# 3_Communication_Buffers.net
KiCad netlist of a schematic drawn in Altium Designer
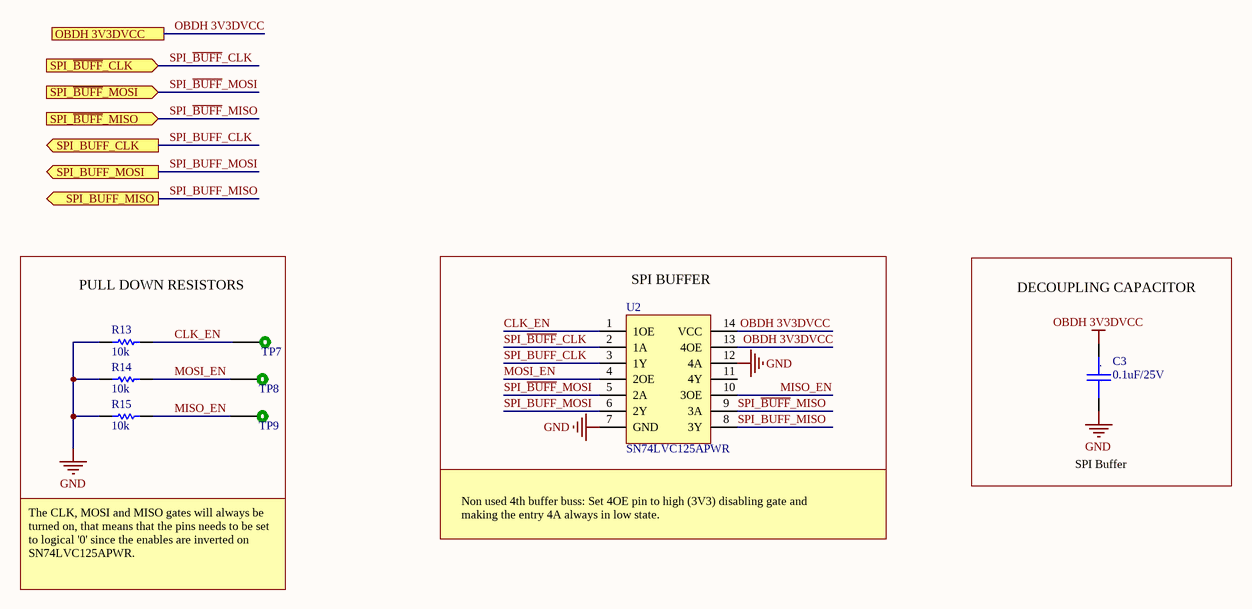
[diagram p0: 3_Communication_Buffers.SchDoc]

(export (version "E")
  (design (tool "Eeschema 10.0.6"))
  (components
    (comp (ref "C3")
      (value "0.1uF/25V")
      (footprint "C0805_MD")
      (description "CAP CER 0.1UF 25V 10% X7R 0805")
      (fields (field (name "PARTNUMBER") "CC0805KRX7R8BB104") (field (name "MANUFACTURER") "Yageo"))
      (libsource (lib "Memory_Expansion_Daughter_Board_SchLib") (part "Cap_Cer_X7R_0.1uF_25V_0805"))
    )
    (comp (ref "R13")
      (value "10k")
      (footprint "0805")
      (description "RES 10K OHM 1/8W 1%  0805")
      (fields (field (name "PARTNUMBER") "CRCW080510K0FKEA") (field (name "MANUFACTURER") "Vishay"))
      (libsource (lib "Memory_Expansion_Daughter_Board_SchLib") (part "R10k_1%_1/8W_0805"))
    )
    (comp (ref "R14")
      (value "10k")
      (footprint "0805")
      (description "RES 10K OHM 1/8W 1%  0805")
      (fields (field (name "PARTNUMBER") "CRCW080510K0FKEA") (field (name "MANUFACTURER") "Vishay"))
      (libsource (lib "Memory_Expansion_Daughter_Board_SchLib") (part "R10k_1%_1/8W_0805"))
    )
    (comp (ref "R15")
      (value "10k")
      (footprint "0805")
      (description "RES 10K OHM 1/8W 1%  0805")
      (fields (field (name "PARTNUMBER") "CRCW080510K0FKEA") (field (name "MANUFACTURER") "Vishay"))
      (libsource (lib "Memory_Expansion_Daughter_Board_SchLib") (part "R10k_1%_1/8W_0805"))
    )
    (comp (ref "TP7")
      (value "TEST_POINT_2")
      (footprint "TEST_POINT_2")
      (description "Test point")
      (libsource (lib "Memory_Expansion_Daughter_Board_SchLib") (part "TEST_POINT_2"))
    )
    (comp (ref "TP8")
      (value "TEST_POINT_2")
      (footprint "TEST_POINT_2")
      (description "Test point")
      (libsource (lib "Memory_Expansion_Daughter_Board_SchLib") (part "TEST_POINT_2"))
    )
    (comp (ref "TP9")
      (value "TEST_POINT_2")
      (footprint "TEST_POINT_2")
      (description "Test point")
      (libsource (lib "Memory_Expansion_Daughter_Board_SchLib") (part "TEST_POINT_2"))
    )
    (comp (ref "U2")
      (value "SN74LVC125APWR")
      (footprint "SN74LVC125APWR")
      (description "IC BUF NON-INVERT 3.6V 14TSSOP")
      (fields (field (name "MANUFACTURER") "Texas Instruments"))
      (libsource (lib "Memory_Expansion_Daughter_Board_SchLib") (part "SN74LVC125APWR"))
    )
  )
  (nets
    (net (code "1") (name "/CLK_EN") (class "Default")
      (node (ref "R13") (pin "1") (pinfunction "1_1") (pintype "passive"))
      (node (ref "TP7") (pin "1") (pinfunction "1_1") (pintype "passive"))
      (node (ref "U2") (pin "1") (pinfunction "1OE_1") (pintype "passive"))
    )
    (net (code "2") (name "/MISO_EN") (class "Default")
      (node (ref "R15") (pin "1") (pinfunction "1_1") (pintype "passive"))
      (node (ref "TP9") (pin "1") (pinfunction "1_1") (pintype "passive"))
      (node (ref "U2") (pin "10") (pinfunction "3OE_10") (pintype "passive"))
    )
    (net (code "3") (name "/MOSI_EN") (class "Default")
      (node (ref "R14") (pin "1") (pinfunction "1_1") (pintype "passive"))
      (node (ref "TP8") (pin "1") (pinfunction "1_1") (pintype "passive"))
      (node (ref "U2") (pin "4") (pinfunction "2OE_4") (pintype "passive"))
    )
    (net (code "4") (name "/SPI_BUFF_CLK") (class "Default")
      (node (ref "U2") (pin "3") (pinfunction "1Y_3") (pintype "passive"))
    )
    (net (code "5") (name "/SPI_BUFF_MISO") (class "Default")
      (node (ref "U2") (pin "8") (pinfunction "3Y_8") (pintype "passive"))
    )
    (net (code "6") (name "/SPI_BUFF_MOSI") (class "Default")
      (node (ref "U2") (pin "6") (pinfunction "2Y_6") (pintype "passive"))
    )
    (net (code "7") (name "/SPI_~{BUFF}_CLK") (class "Default")
      (node (ref "U2") (pin "2") (pinfunction "1A_2") (pintype "passive"))
    )
    (net (code "8") (name "/SPI_~{BUFF}_MISO") (class "Default")
      (node (ref "U2") (pin "9") (pinfunction "3A_9") (pintype "passive"))
    )
    (net (code "9") (name "/SPI_~{BUFF}_MOSI") (class "Default")
      (node (ref "U2") (pin "5") (pinfunction "2A_5") (pintype "passive"))
    )
    (net (code "10") (name "GND") (class "Default")
      (node (ref "C3") (pin "2") (pinfunction "2_2") (pintype "passive"))
      (node (ref "R13") (pin "2") (pinfunction "2_2") (pintype "passive"))
      (node (ref "R14") (pin "2") (pinfunction "2_2") (pintype "passive"))
      (node (ref "R15") (pin "2") (pinfunction "2_2") (pintype "passive"))
      (node (ref "U2") (pin "12") (pinfunction "4A_12") (pintype "passive"))
      (node (ref "U2") (pin "7") (pinfunction "GND_7") (pintype "passive"))
    )
    (net (code "11") (name "OBDH 3V3DVCC") (class "Default")
      (node (ref "C3") (pin "1") (pinfunction "1_1") (pintype "passive"))
      (node (ref "U2") (pin "13") (pinfunction "4OE_13") (pintype "passive"))
      (node (ref "U2") (pin "14") (pinfunction "VCC_14") (pintype "passive"))
    )
    (net (code "12") (name "unconnected-(U2-4Y-Pad11)") (class "Default")
      (node (ref "U2") (pin "11") (pinfunction "4Y_11") (pintype "passive"))
    )
  )
)
